# design.net
KiCad netlist of a schematic drawn in EasyEDA Pro
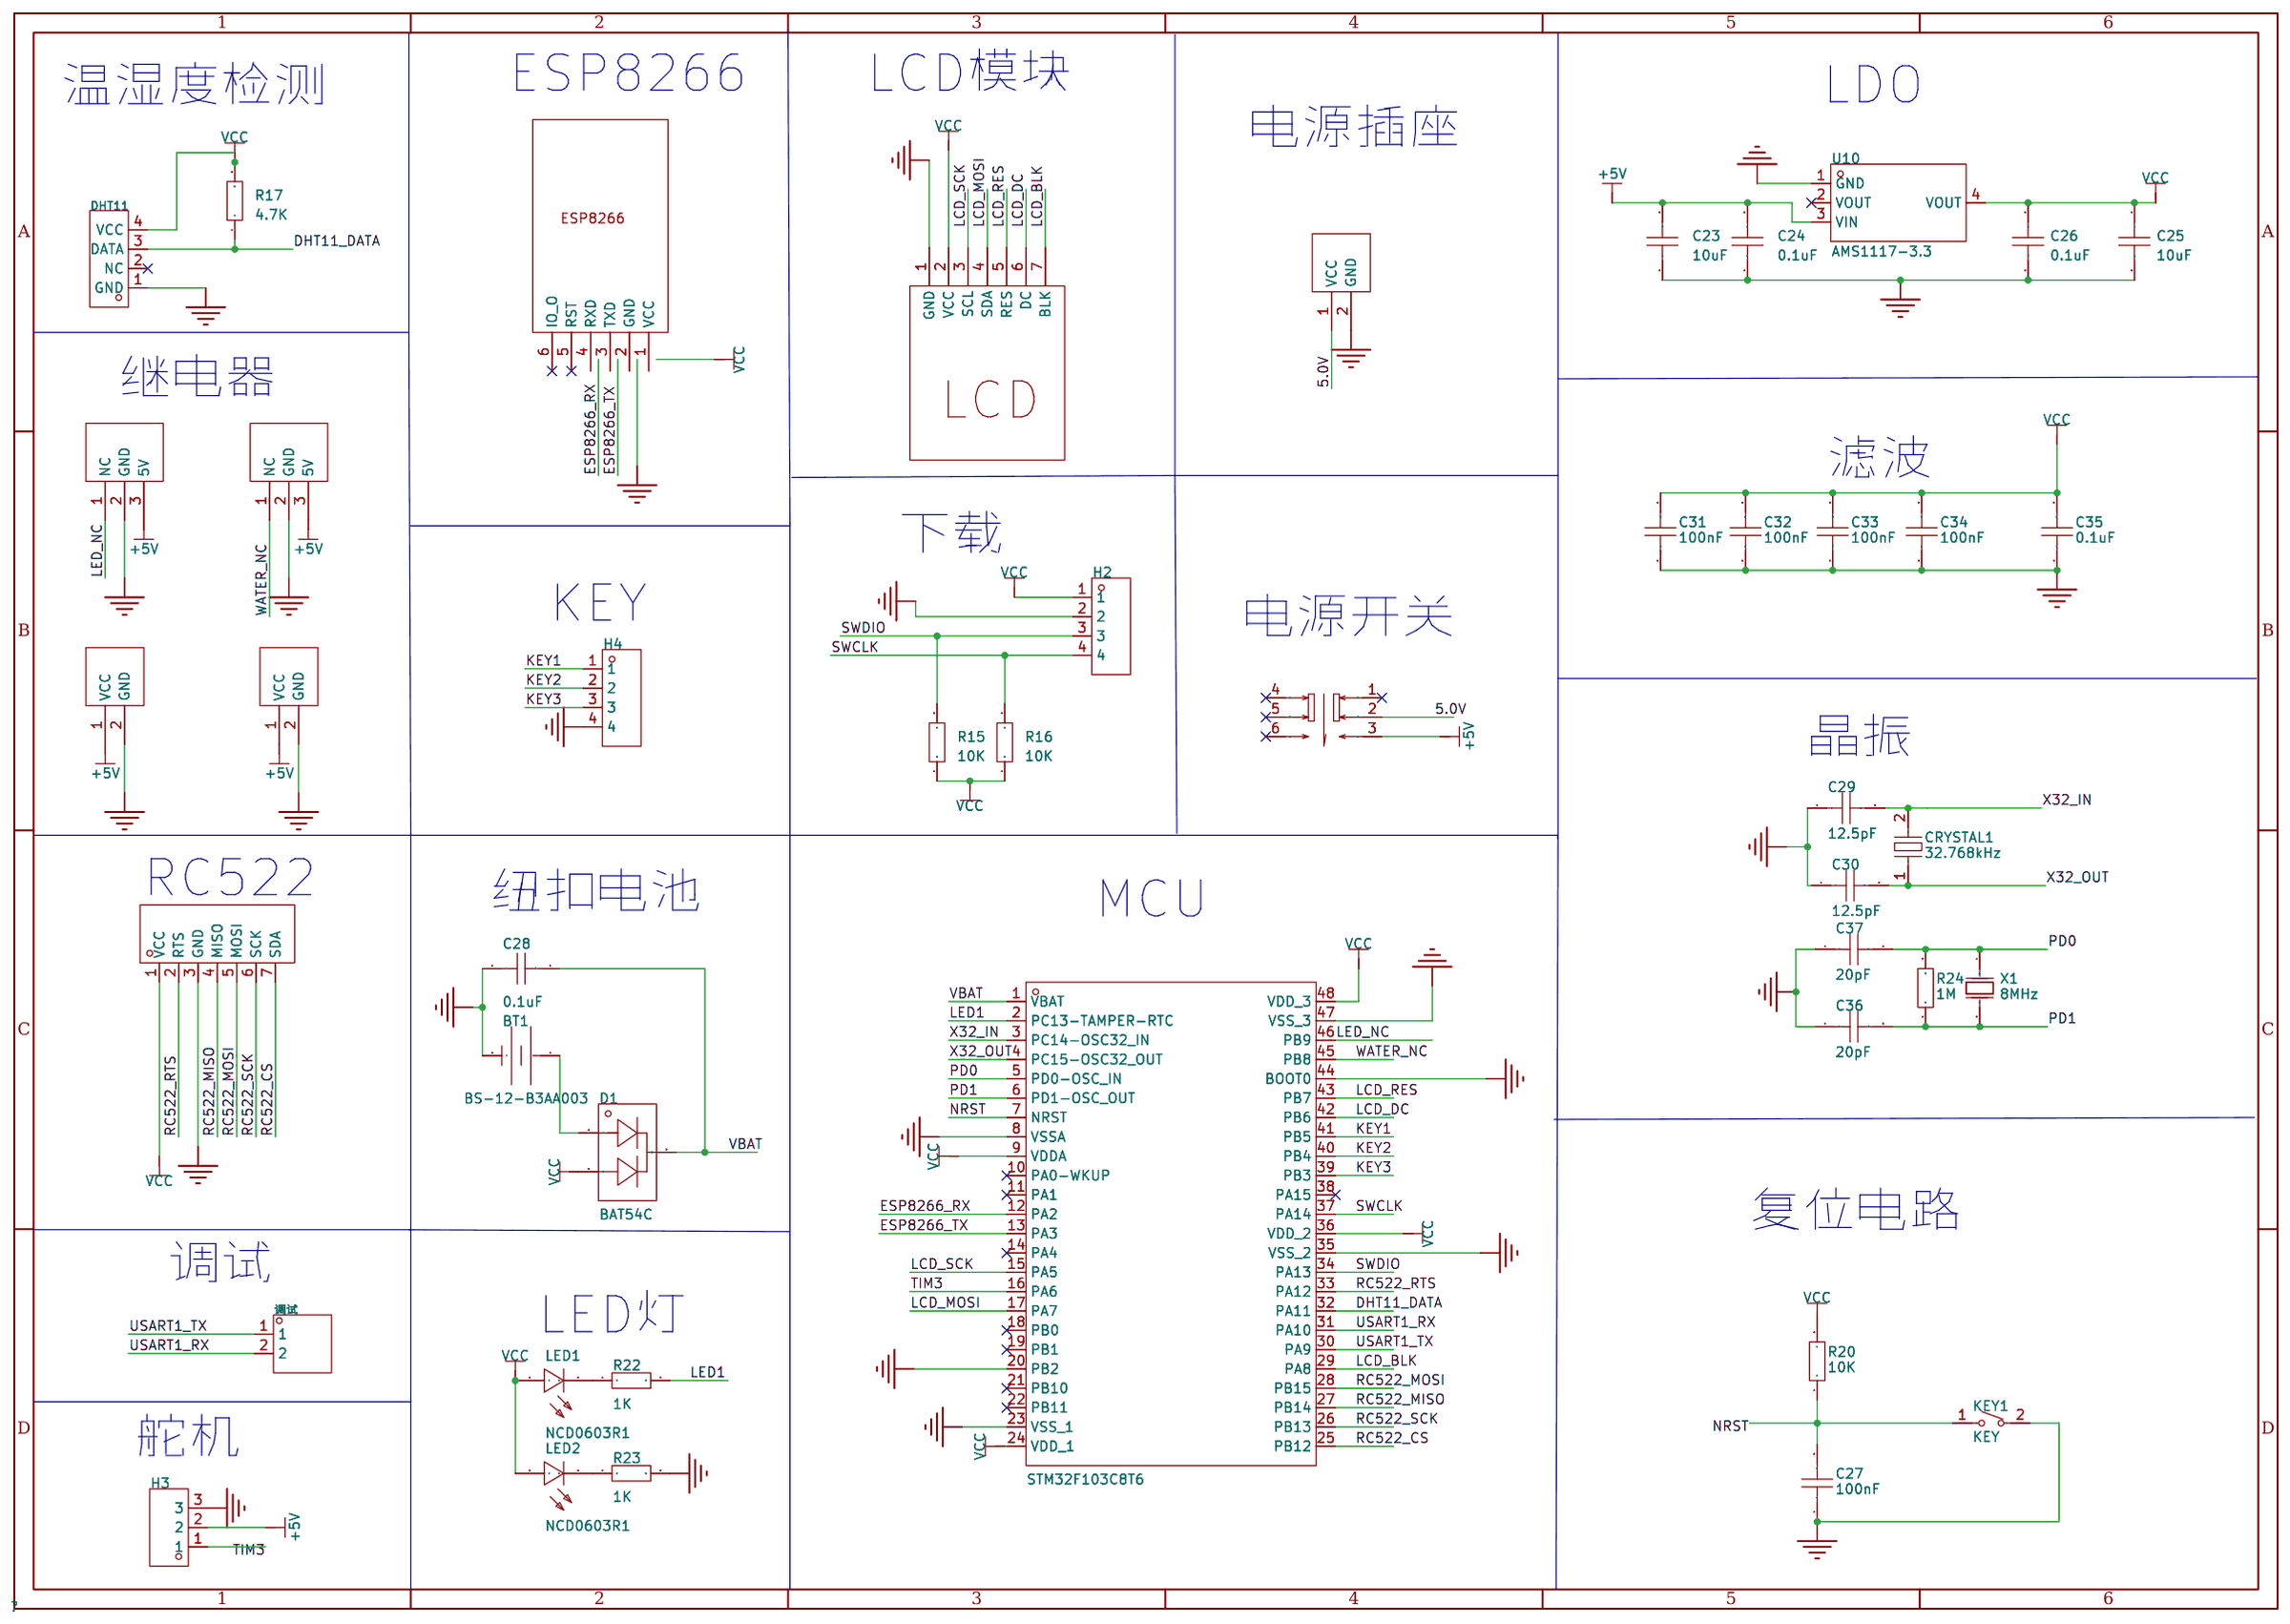
[diagram p0: schematic sheet]

(export (version "E")
  (design (tool "Eeschema 10.0.6"))
  (components
    (comp (ref "BT1")
      (value "BS-12-B3AA003")
      (footprint "easyedapro:BAT-SMD_BS-12-B3AA011")
      (description "连接器类型:电池底座;适用电池规格:CR1220;工作温度范围:-25°C~+85°C;")
      (fields (field (name "Manufacturer") "MYOUNG(美阳)"))
      (libsource (lib "easyedapro") (part "BS-12-B3AA003"))
    )
    (comp (ref "C23")
      (value "10uF")
      (footprint "easyedapro:C0402")
      (libsource (lib "easyedapro") (part "CapAcitance"))
    )
    (comp (ref "C24")
      (value "0.1uF")
      (footprint "easyedapro:C0402")
      (libsource (lib "easyedapro") (part "CapAcitance"))
    )
    (comp (ref "C25")
      (value "10uF")
      (footprint "easyedapro:C0402")
      (libsource (lib "easyedapro") (part "CapAcitance"))
    )
    (comp (ref "C26")
      (value "0.1uF")
      (footprint "easyedapro:C0402")
      (libsource (lib "easyedapro") (part "CapAcitance"))
    )
    (comp (ref "C27")
      (value "100nF")
      (footprint "easyedapro:C0402")
      (libsource (lib "easyedapro") (part "CapAcitance"))
    )
    (comp (ref "C28")
      (value "0.1uF")
      (footprint "easyedapro:C0402")
      (libsource (lib "easyedapro") (part "CapAcitance"))
    )
    (comp (ref "C29")
      (value "12.5pF")
      (footprint "easyedapro:C0402")
      (libsource (lib "easyedapro") (part "CapAcitance"))
    )
    (comp (ref "C30")
      (value "12.5pF")
      (footprint "easyedapro:C0402")
      (libsource (lib "easyedapro") (part "CapAcitance"))
    )
    (comp (ref "C31")
      (value "100nF")
      (footprint "easyedapro:C0402")
      (libsource (lib "easyedapro") (part "CapAcitance"))
    )
    (comp (ref "C32")
      (value "100nF")
      (footprint "easyedapro:C0402")
      (libsource (lib "easyedapro") (part "CapAcitance"))
    )
    (comp (ref "C33")
      (value "100nF")
      (footprint "easyedapro:C0402")
      (libsource (lib "easyedapro") (part "CapAcitance"))
    )
    (comp (ref "C34")
      (value "100nF")
      (footprint "easyedapro:C0402")
      (libsource (lib "easyedapro") (part "CapAcitance"))
    )
    (comp (ref "C35")
      (value "0.1uF")
      (footprint "easyedapro:C0402")
      (libsource (lib "easyedapro") (part "CapAcitance"))
    )
    (comp (ref "C36")
      (value "20pF")
      (footprint "easyedapro:C0402")
      (libsource (lib "easyedapro") (part "CapAcitance"))
    )
    (comp (ref "C37")
      (value "20pF")
      (footprint "easyedapro:C0402")
      (libsource (lib "easyedapro") (part "CapAcitance"))
    )
    (comp (ref "CRYSTAL1")
      (value "32.768kHz")
      (footprint "easyedapro:CRYSTAL-SMD_L3.2-W1.5-FC-135R32.7680KF-A3")
      (description "频率:32.768kHz;负载电容:12.5pF;频率公差:±20ppm;")
      (fields (field (name "Manufacturer Part") "DF2032K76812001") (field (name "Manufacturer") "HUAXIN(华昕)"))
      (libsource (lib "easyedapro") (part "DF2032K76812001"))
    )
    (comp (ref "D1")
      (value "BAT54C")
      (footprint "easyedapro:SOT-23-3_L2.9-W1.4-P1.91-LS2.6-BR")
      (description "二极管配置:1对共阴极;正向压降(Vf):1V@100mA;直流反向耐压(Vr):30V;平均整流电流(Io):200mA;")
      (fields (field (name "Manufacturer") "TWGMC(台湾迪嘉)"))
      (libsource (lib "easyedapro") (part "BAT54C_C727125"))
    )
    (comp (ref "DHT11")
      (value "~")
      (footprint "easyedapro:HDR-TH_4P-P2.54-V-F")
      (fields (field (name "Manufacturer Part") "2.54-1*4P母") (field (name "Manufacturer") "BOOMELE(博穆精密)"))
      (libsource (lib "easyedapro") (part "2.54-1*4P母"))
    )
    (comp (ref "H1")
      (value "~")
      (footprint "easyedapro:HDR-TH_7P-P2.54-V-M")
      (fields (field (name "Manufacturer Part") "PZ254V-11-07P") (field (name "Manufacturer") "XFCN(兴飞)"))
      (libsource (lib "easyedapro") (part "PZ254V-11-07P"))
    )
    (comp (ref "H2")
      (value "~")
      (footprint "easyedapro:HDR-TH_4P-P2.54-V-M")
      (libsource (lib "easyedapro") (part "PZ254V-11-04P"))
    )
    (comp (ref "H3")
      (value "~")
      (footprint "easyedapro:HDR-TH_3P-P2.54-V-M")
      (libsource (lib "easyedapro") (part "PZ254V-11-03P_C2937625"))
    )
    (comp (ref "H4")
      (value "~")
      (footprint "easyedapro:HDR-TH_4P-P2.54-V-M")
      (libsource (lib "easyedapro") (part "PZ254V-11-04P"))
    )
    (comp (ref "KEY1")
      (value "KEY")
      (footprint "easyedapro:SW-SMD_L6.0-W3.7-LS8.0")
      (libsource (lib "easyedapro") (part "KEY_C9900023212"))
    )
    (comp (ref "LED1")
      (value "NCD0603R1")
      (footprint "easyedapro:LED0603-RD_RED")
      (description "发光颜色:红色;功率:65mW;透镜颜色:无色透明;主波长:615nm~630nm;发光强度:80mcd~220mcd;发光角度:130°;工作温度:-30°C~+85°C;")
      (fields (field (name "Manufacturer") "国星光电"))
      (libsource (lib "easyedapro") (part "FC-DA1608HRK-620D"))
    )
    (comp (ref "LED2")
      (value "NCD0603R1")
      (footprint "easyedapro:LED0603-RD_RED")
      (description "发光颜色:红色;功率:65mW;透镜颜色:无色透明;主波长:615nm~630nm;发光强度:80mcd~220mcd;发光角度:130°;工作温度:-30°C~+85°C;")
      (fields (field (name "Manufacturer") "国星光电"))
      (libsource (lib "easyedapro") (part "FC-DA1608HRK-620D"))
    )
    (comp (ref "R15")
      (value "10K")
      (footprint "easyedapro:Res_1/8W")
      (libsource (lib "easyedapro") (part "电阻"))
    )
    (comp (ref "R16")
      (value "10K")
      (footprint "easyedapro:Res_1/8W")
      (libsource (lib "easyedapro") (part "电阻"))
    )
    (comp (ref "R17")
      (value "4.7K")
      (footprint "easyedapro:Res_1/8W")
      (libsource (lib "easyedapro") (part "电阻"))
    )
    (comp (ref "R20")
      (value "10K")
      (footprint "easyedapro:Res_1/8W")
      (libsource (lib "easyedapro") (part "电阻"))
    )
    (comp (ref "R22")
      (value "1K")
      (footprint "easyedapro:Res_1/8W")
      (libsource (lib "easyedapro") (part "电阻"))
    )
    (comp (ref "R23")
      (value "1K")
      (footprint "easyedapro:Res_1/8W")
      (libsource (lib "easyedapro") (part "电阻"))
    )
    (comp (ref "R24")
      (value "1M")
      (footprint "easyedapro:Res_1/8W")
      (libsource (lib "easyedapro") (part "电阻"))
    )
    (comp (ref "SW1")
      (value "TK-6700-1")
      (footprint "easyedapro:SW-TH_TK-6700-1")
      (fields (field (name "Manufacturer") "Yuandi(元迪)"))
      (libsource (lib "easyedapro") (part "TK-6700-1"))
    )
    (comp (ref "U1")
      (value "~")
      (footprint "easyedapro:正点原子ESP8266")
      (libsource (lib "easyedapro") (part "正点原子ESP8266"))
    )
    (comp (ref "U2")
      (value "~")
      (footprint "easyedapro:LCD-TFT")
      (libsource (lib "easyedapro") (part "LCD-TFT"))
    )
    (comp (ref "U3")
      (value "~")
      (footprint "easyedapro:电源2Pin")
      (libsource (lib "easyedapro") (part "电源2Pin"))
    )
    (comp (ref "U5")
      (value "~")
      (footprint "easyedapro:电源3Pin")
      (libsource (lib "easyedapro") (part "电源3Pin"))
    )
    (comp (ref "U6")
      (value "~")
      (footprint "easyedapro:电源3Pin")
      (libsource (lib "easyedapro") (part "电源3Pin"))
    )
    (comp (ref "U7")
      (value "~")
      (footprint "easyedapro:电源2Pin")
      (libsource (lib "easyedapro") (part "电源2Pin"))
    )
    (comp (ref "U8")
      (value "~")
      (footprint "easyedapro:电源2Pin")
      (libsource (lib "easyedapro") (part "电源2Pin"))
    )
    (comp (ref "U9")
      (value "STM32F103C8T6")
      (footprint "easyedapro:LQFP-48_L7.0-W7.0-P0.50-LS9.0-BL")
      (fields (field (name "Manufacturer") "ST(意法半导体)"))
      (libsource (lib "easyedapro") (part "STM32F103C8T6"))
    )
    (comp (ref "U10")
      (value "AMS1117-3.3")
      (footprint "easyedapro:SOT-223-3_L6.5-W3.4-P2.30-LS7.0-BR")
      (description "输出类型:固定;最大输入电压:-;输出电压:3.3V;输出电流:1A;电源纹波抑制比(PSRR):72dB@(120Hz);输出极性:正;")
      (fields (field (name "Manufacturer") "AMS"))
      (libsource (lib "easyedapro") (part "AMS1117-3.3"))
    )
    (comp (ref "X1")
      (value "8MHz")
      (footprint "easyedapro:CRYSTAL-SMD_L11.5-W4.8-LS12.7")
      (description "频率:8MHz;负载电容:20pF;频率公差:±20ppm;")
      (fields (field (name "Manufacturer Part") "X49SM8MSD2SC") (field (name "Manufacturer") "YXC(扬兴晶振)"))
      (libsource (lib "easyedapro") (part "X49SM8MSD2SC"))
    )
    (comp (ref "调试")
      (value "~")
      (footprint "easyedapro:HDR-TH_2P-P2.54-V-M-1")
      (libsource (lib "easyedapro") (part "210S-1*2P L=11.6MMGold-plated black"))
    )
  )
  (nets
    (net (code "1") (name "+5V") (class "Default")
      (node (ref "C23") (pin "2") (pinfunction "2_2") (pintype "input"))
      (node (ref "C24") (pin "2") (pinfunction "2_2") (pintype "input"))
      (node (ref "H3") (pin "2") (pinfunction "2_2") (pintype "input"))
      (node (ref "SW1") (pin "3") (pinfunction "3_3") (pintype "input"))
      (node (ref "U10") (pin "3") (pinfunction "VIN_3") (pintype "unspecified"))
      (node (ref "U5") (pin "3") (pinfunction "5V_3") (pintype "input"))
      (node (ref "U6") (pin "3") (pinfunction "5V_3") (pintype "input"))
      (node (ref "U7") (pin "1") (pinfunction "VCC_1") (pintype "input"))
      (node (ref "U8") (pin "1") (pinfunction "VCC_1") (pintype "input"))
    )
    (net (code "2") (name "/5.0V") (class "Default")
      (node (ref "SW1") (pin "2") (pinfunction "2_2") (pintype "input"))
      (node (ref "U3") (pin "1") (pinfunction "VCC_1") (pintype "input"))
    )
    (net (code "3") (name "/DHT11_DATA") (class "Default")
      (node (ref "DHT11") (pin "3") (pinfunction "DATA_3") (pintype "input"))
      (node (ref "R17") (pin "1") (pinfunction "1_1") (pintype "input"))
      (node (ref "U9") (pin "32") (pinfunction "PA11_32") (pintype "unspecified"))
    )
    (net (code "4") (name "/ESP8266_RX") (class "Default")
      (node (ref "U9") (pin "12") (pinfunction "PA2_12") (pintype "unspecified"))
    )
    (net (code "5") (name "/ESP8266_TX") (class "Default")
      (node (ref "U9") (pin "13") (pinfunction "PA3_13") (pintype "unspecified"))
    )
    (net (code "6") (name "/KEY1") (class "Default")
      (node (ref "H4") (pin "1") (pinfunction "1_1") (pintype "unspecified"))
      (node (ref "U9") (pin "41") (pinfunction "PB5_41") (pintype "unspecified"))
    )
    (net (code "7") (name "/KEY2") (class "Default")
      (node (ref "H4") (pin "2") (pinfunction "2_2") (pintype "unspecified"))
      (node (ref "U9") (pin "40") (pinfunction "PB4_40") (pintype "unspecified"))
    )
    (net (code "8") (name "/KEY3") (class "Default")
      (node (ref "H4") (pin "3") (pinfunction "3_3") (pintype "unspecified"))
      (node (ref "U9") (pin "39") (pinfunction "PB3_39") (pintype "unspecified"))
    )
    (net (code "9") (name "/LCD_BLK") (class "Default")
      (node (ref "U2") (pin "7") (pinfunction "BLK_7") (pintype "input"))
      (node (ref "U9") (pin "29") (pinfunction "PA8_29") (pintype "unspecified"))
    )
    (net (code "10") (name "/LCD_DC") (class "Default")
      (node (ref "U2") (pin "6") (pinfunction "DC_6") (pintype "input"))
      (node (ref "U9") (pin "42") (pinfunction "PB6_42") (pintype "unspecified"))
    )
    (net (code "11") (name "/LCD_MOSI") (class "Default")
      (node (ref "U2") (pin "4") (pinfunction "SDA_4") (pintype "input"))
      (node (ref "U9") (pin "17") (pinfunction "PA7_17") (pintype "unspecified"))
    )
    (net (code "12") (name "/LCD_RES") (class "Default")
      (node (ref "U2") (pin "5") (pinfunction "RES_5") (pintype "input"))
      (node (ref "U9") (pin "43") (pinfunction "PB7_43") (pintype "unspecified"))
    )
    (net (code "13") (name "/LCD_SCK") (class "Default")
      (node (ref "U2") (pin "3") (pinfunction "SCL_3") (pintype "input"))
      (node (ref "U9") (pin "15") (pinfunction "PA5_15") (pintype "unspecified"))
    )
    (net (code "14") (name "/LED1") (class "Default")
      (node (ref "R22") (pin "2") (pinfunction "2_2") (pintype "input"))
      (node (ref "U9") (pin "2") (pinfunction "PC13-TAMPER-RTC_2") (pintype "unspecified"))
    )
    (net (code "15") (name "/LED_NC") (class "Default")
      (node (ref "U5") (pin "1") (pinfunction "NC_1") (pintype "input"))
      (node (ref "U9") (pin "46") (pinfunction "PB9_46") (pintype "unspecified"))
    )
    (net (code "16") (name "/NRST") (class "Default")
      (node (ref "C27") (pin "2") (pinfunction "2_2") (pintype "input"))
      (node (ref "KEY1") (pin "1") (pinfunction "1_1") (pintype "input"))
      (node (ref "R20") (pin "1") (pinfunction "1_1") (pintype "input"))
      (node (ref "U9") (pin "7") (pinfunction "NRST_7") (pintype "unspecified"))
    )
    (net (code "17") (name "/PD0") (class "Default")
      (node (ref "C37") (pin "2") (pinfunction "2_2") (pintype "input"))
      (node (ref "R24") (pin "2") (pinfunction "2_2") (pintype "input"))
      (node (ref "U9") (pin "5") (pinfunction "PD0-OSC_IN_5") (pintype "unspecified"))
      (node (ref "X1") (pin "1") (pinfunction "OSC1_1") (pintype "input"))
    )
    (net (code "18") (name "/PD1") (class "Default")
      (node (ref "C36") (pin "2") (pinfunction "2_2") (pintype "input"))
      (node (ref "R24") (pin "1") (pinfunction "1_1") (pintype "input"))
      (node (ref "U9") (pin "6") (pinfunction "PD1-OSC_OUT_6") (pintype "unspecified"))
      (node (ref "X1") (pin "2") (pinfunction "OSC2_2") (pintype "input"))
    )
    (net (code "19") (name "/RC522_CS") (class "Default")
      (node (ref "H1") (pin "7") (pinfunction "SDA_7") (pintype "input"))
      (node (ref "U9") (pin "25") (pinfunction "PB12_25") (pintype "unspecified"))
    )
    (net (code "20") (name "/RC522_MISO") (class "Default")
      (node (ref "H1") (pin "4") (pinfunction "MISO_4") (pintype "input"))
      (node (ref "U9") (pin "27") (pinfunction "PB14_27") (pintype "unspecified"))
    )
    (net (code "21") (name "/RC522_MOSI") (class "Default")
      (node (ref "H1") (pin "5") (pinfunction "MOSI_5") (pintype "input"))
      (node (ref "U9") (pin "28") (pinfunction "PB15_28") (pintype "unspecified"))
    )
    (net (code "22") (name "/RC522_RTS") (class "Default")
      (node (ref "H1") (pin "2") (pinfunction "RTS_2") (pintype "input"))
      (node (ref "U9") (pin "33") (pinfunction "PA12_33") (pintype "unspecified"))
    )
    (net (code "23") (name "/RC522_SCK") (class "Default")
      (node (ref "H1") (pin "6") (pinfunction "SCK_6") (pintype "input"))
      (node (ref "U9") (pin "26") (pinfunction "PB13_26") (pintype "unspecified"))
    )
    (net (code "24") (name "/SWCLK") (class "Default")
      (node (ref "H2") (pin "4") (pinfunction "4_4") (pintype "unspecified"))
      (node (ref "R16") (pin "2") (pinfunction "2_2") (pintype "input"))
      (node (ref "U9") (pin "37") (pinfunction "PA14_37") (pintype "unspecified"))
    )
    (net (code "25") (name "/SWDIO") (class "Default")
      (node (ref "H2") (pin "3") (pinfunction "3_3") (pintype "unspecified"))
      (node (ref "R15") (pin "2") (pinfunction "2_2") (pintype "input"))
      (node (ref "U9") (pin "34") (pinfunction "PA13_34") (pintype "unspecified"))
    )
    (net (code "26") (name "/TIM3") (class "Default")
      (node (ref "H3") (pin "1") (pinfunction "1_1") (pintype "input"))
      (node (ref "U9") (pin "16") (pinfunction "PA6_16") (pintype "unspecified"))
    )
    (net (code "27") (name "/USART1_RX") (class "Default")
      (node (ref "U9") (pin "31") (pinfunction "PA10_31") (pintype "unspecified"))
      (node (ref "调试") (pin "2") (pinfunction "2_2") (pintype "input"))
    )
    (net (code "28") (name "/USART1_TX") (class "Default")
      (node (ref "U9") (pin "30") (pinfunction "PA9_30") (pintype "unspecified"))
      (node (ref "调试") (pin "1") (pinfunction "1_1") (pintype "input"))
    )
    (net (code "29") (name "/VBAT") (class "Default")
      (node (ref "C28") (pin "2") (pinfunction "2_2") (pintype "input"))
      (node (ref "D1") (pin "3") (pinfunction "3_3") (pintype "unspecified"))
      (node (ref "U9") (pin "1") (pinfunction "VBAT_1") (pintype "unspecified"))
    )
    (net (code "30") (name "/WATER_NC") (class "Default")
      (node (ref "U6") (pin "1") (pinfunction "NC_1") (pintype "input"))
      (node (ref "U9") (pin "45") (pinfunction "PB8_45") (pintype "unspecified"))
    )
    (net (code "31") (name "/X32_IN") (class "Default")
      (node (ref "C29") (pin "2") (pinfunction "2_2") (pintype "input"))
      (node (ref "CRYSTAL1") (pin "2") (pinfunction "2_2") (pintype "unspecified"))
      (node (ref "U9") (pin "3") (pinfunction "PC14-OSC32_IN_3") (pintype "unspecified"))
    )
    (net (code "32") (name "/X32_OUT") (class "Default")
      (node (ref "C30") (pin "2") (pinfunction "2_2") (pintype "input"))
      (node (ref "CRYSTAL1") (pin "1") (pinfunction "1_1") (pintype "unspecified"))
      (node (ref "U9") (pin "4") (pinfunction "PC15-OSC32_OUT_4") (pintype "unspecified"))
    )
    (net (code "33") (name "GND") (class "Default")
      (node (ref "BT1") (pin "2") (pinfunction "-_2") (pintype "unspecified"))
      (node (ref "C23") (pin "1") (pinfunction "1_1") (pintype "input"))
      (node (ref "C24") (pin "1") (pinfunction "1_1") (pintype "input"))
      (node (ref "C25") (pin "2") (pinfunction "2_2") (pintype "input"))
      (node (ref "C26") (pin "2") (pinfunction "2_2") (pintype "input"))
      (node (ref "C27") (pin "1") (pinfunction "1_1") (pintype "input"))
      (node (ref "C28") (pin "1") (pinfunction "1_1") (pintype "input"))
      (node (ref "C29") (pin "1") (pinfunction "1_1") (pintype "input"))
      (node (ref "C30") (pin "1") (pinfunction "1_1") (pintype "input"))
      (node (ref "C31") (pin "1") (pinfunction "1_1") (pintype "input"))
      (node (ref "C32") (pin "1") (pinfunction "1_1") (pintype "input"))
      (node (ref "C33") (pin "1") (pinfunction "1_1") (pintype "input"))
      (node (ref "C34") (pin "1") (pinfunction "1_1") (pintype "input"))
      (node (ref "C35") (pin "1") (pinfunction "1_1") (pintype "input"))
      (node (ref "C36") (pin "1") (pinfunction "1_1") (pintype "input"))
      (node (ref "C37") (pin "1") (pinfunction "1_1") (pintype "input"))
      (node (ref "DHT11") (pin "1") (pinfunction "GND_1") (pintype "input"))
      (node (ref "H1") (pin "3") (pinfunction "GND_3") (pintype "input"))
      (node (ref "H2") (pin "2") (pinfunction "2_2") (pintype "unspecified"))
      (node (ref "H3") (pin "3") (pinfunction "3_3") (pintype "input"))
      (node (ref "H4") (pin "4") (pinfunction "4_4") (pintype "unspecified"))
      (node (ref "KEY1") (pin "2") (pinfunction "2_2") (pintype "input"))
      (node (ref "R23") (pin "2") (pinfunction "2_2") (pintype "input"))
      (node (ref "U10") (pin "1") (pinfunction "GND_1") (pintype "unspecified"))
      (node (ref "U2") (pin "1") (pinfunction "GND_1") (pintype "input"))
      (node (ref "U3") (pin "2") (pinfunction "GND_2") (pintype "input"))
      (node (ref "U5") (pin "2") (pinfunction "GND_2") (pintype "input"))
      (node (ref "U6") (pin "2") (pinfunction "GND_2") (pintype "input"))
      (node (ref "U7") (pin "2") (pinfunction "GND_2") (pintype "input"))
      (node (ref "U8") (pin "2") (pinfunction "GND_2") (pintype "input"))
      (node (ref "U9") (pin "20") (pinfunction "PB2_20") (pintype "unspecified"))
      (node (ref "U9") (pin "23") (pinfunction "VSS_1_23") (pintype "unspecified"))
      (node (ref "U9") (pin "35") (pinfunction "VSS_2_35") (pintype "unspecified"))
      (node (ref "U9") (pin "44") (pinfunction "BOOT0_44") (pintype "unspecified"))
      (node (ref "U9") (pin "47") (pinfunction "VSS_3_47") (pintype "unspecified"))
      (node (ref "U9") (pin "8") (pinfunction "VSSA_8") (pintype "unspecified"))
    )
    (net (code "34") (name "Net-(BT1-+)") (class "Default")
      (node (ref "BT1") (pin "1") (pinfunction "+_1") (pintype "unspecified"))
      (node (ref "D1") (pin "1") (pinfunction "1_1") (pintype "unspecified"))
    )
    (net (code "35") (name "Net-(LED1-K)") (class "Default")
      (node (ref "LED1") (pin "1") (pinfunction "K_1") (pintype "input"))
      (node (ref "R22") (pin "1") (pinfunction "1_1") (pintype "input"))
    )
    (net (code "36") (name "Net-(LED2-K)") (class "Default")
      (node (ref "LED2") (pin "1") (pinfunction "K_1") (pintype "input"))
      (node (ref "R23") (pin "1") (pinfunction "1_1") (pintype "input"))
    )
    (net (code "37") (name "VCC") (class "Default")
      (node (ref "C25") (pin "1") (pinfunction "1_1") (pintype "input"))
      (node (ref "C26") (pin "1") (pinfunction "1_1") (pintype "input"))
      (node (ref "C31") (pin "2") (pinfunction "2_2") (pintype "input"))
      (node (ref "C32") (pin "2") (pinfunction "2_2") (pintype "input"))
      (node (ref "C33") (pin "2") (pinfunction "2_2") (pintype "input"))
      (node (ref "C34") (pin "2") (pinfunction "2_2") (pintype "input"))
      (node (ref "C35") (pin "2") (pinfunction "2_2") (pintype "input"))
      (node (ref "D1") (pin "2") (pinfunction "2_2") (pintype "unspecified"))
      (node (ref "DHT11") (pin "4") (pinfunction "VCC_4") (pintype "input"))
      (node (ref "H1") (pin "1") (pinfunction "VCC_1") (pintype "input"))
      (node (ref "H2") (pin "1") (pinfunction "1_1") (pintype "unspecified"))
      (node (ref "LED1") (pin "2") (pinfunction "A_2") (pintype "input"))
      (node (ref "LED2") (pin "2") (pinfunction "A_2") (pintype "input"))
      (node (ref "R15") (pin "1") (pinfunction "1_1") (pintype "input"))
      (node (ref "R16") (pin "1") (pinfunction "1_1") (pintype "input"))
      (node (ref "R17") (pin "2") (pinfunction "2_2") (pintype "input"))
      (node (ref "R20") (pin "2") (pinfunction "2_2") (pintype "input"))
      (node (ref "U10") (pin "4") (pinfunction "VOUT_4") (pintype "unspecified"))
      (node (ref "U2") (pin "2") (pinfunction "VCC_2") (pintype "input"))
      (node (ref "U9") (pin "24") (pinfunction "VDD_1_24") (pintype "unspecified"))
      (node (ref "U9") (pin "36") (pinfunction "VDD_2_36") (pintype "unspecified"))
      (node (ref "U9") (pin "48") (pinfunction "VDD_3_48") (pintype "unspecified"))
      (node (ref "U9") (pin "9") (pinfunction "VDDA_9") (pintype "unspecified"))
    )
    (net (code "38") (name "unconnected-(DHT11-NC-Pad2)") (class "Default")
      (node (ref "DHT11") (pin "2") (pinfunction "NC_2") (pintype "input+no_connect"))
    )
    (net (code "39") (name "unconnected-(SW1-Pad1)") (class "Default")
      (node (ref "SW1") (pin "1") (pinfunction "1_1") (pintype "input+no_connect"))
    )
    (net (code "40") (name "unconnected-(SW1-Pad4)") (class "Default")
      (node (ref "SW1") (pin "4") (pinfunction "4_4") (pintype "input+no_connect"))
    )
    (net (code "41") (name "unconnected-(SW1-Pad5)") (class "Default")
      (node (ref "SW1") (pin "5") (pinfunction "5_5") (pintype "input+no_connect"))
    )
    (net (code "42") (name "unconnected-(SW1-Pad6)") (class "Default")
      (node (ref "SW1") (pin "6") (pinfunction "6_6") (pintype "input+no_connect"))
    )
    (net (code "43") (name "unconnected-(U1-GND-Pad2)") (class "Default")
      (node (ref "U1") (pin "2") (pinfunction "GND_2") (pintype "input"))
    )
    (net (code "44") (name "unconnected-(U1-IO_O-Pad6)") (class "Default")
      (node (ref "U1") (pin "6") (pinfunction "IO_O_6") (pintype "input+no_connect"))
    )
    (net (code "45") (name "unconnected-(U1-RST-Pad5)") (class "Default")
      (node (ref "U1") (pin "5") (pinfunction "RST_5") (pintype "input+no_connect"))
    )
    (net (code "46") (name "unconnected-(U1-RXD-Pad4)") (class "Default")
      (node (ref "U1") (pin "4") (pinfunction "RXD_4") (pintype "input"))
    )
    (net (code "47") (name "unconnected-(U1-TXD-Pad3)") (class "Default")
      (node (ref "U1") (pin "3") (pinfunction "TXD_3") (pintype "input"))
    )
    (net (code "48") (name "unconnected-(U1-VCC-Pad1)") (class "Default")
      (node (ref "U1") (pin "1") (pinfunction "VCC_1") (pintype "input"))
    )
    (net (code "49") (name "unconnected-(U9-PA0-WKUP-Pad10)") (class "Default")
      (node (ref "U9") (pin "10") (pinfunction "PA0-WKUP_10") (pintype "unspecified+no_connect"))
    )
    (net (code "50") (name "unconnected-(U9-PA1-Pad11)") (class "Default")
      (node (ref "U9") (pin "11") (pinfunction "PA1_11") (pintype "unspecified+no_connect"))
    )
    (net (code "51") (name "unconnected-(U9-PA4-Pad14)") (class "Default")
      (node (ref "U9") (pin "14") (pinfunction "PA4_14") (pintype "unspecified+no_connect"))
    )
    (net (code "52") (name "unconnected-(U9-PA15-Pad38)") (class "Default")
      (node (ref "U9") (pin "38") (pinfunction "PA15_38") (pintype "unspecified+no_connect"))
    )
    (net (code "53") (name "unconnected-(U9-PB0-Pad18)") (class "Default")
      (node (ref "U9") (pin "18") (pinfunction "PB0_18") (pintype "unspecified+no_connect"))
    )
    (net (code "54") (name "unconnected-(U9-PB1-Pad19)") (class "Default")
      (node (ref "U9") (pin "19") (pinfunction "PB1_19") (pintype "unspecified+no_connect"))
    )
    (net (code "55") (name "unconnected-(U9-PB10-Pad21)") (class "Default")
      (node (ref "U9") (pin "21") (pinfunction "PB10_21") (pintype "unspecified+no_connect"))
    )
    (net (code "56") (name "unconnected-(U9-PB11-Pad22)") (class "Default")
      (node (ref "U9") (pin "22") (pinfunction "PB11_22") (pintype "unspecified+no_connect"))
    )
    (net (code "57") (name "unconnected-(U10-VOUT-Pad2)") (class "Default")
      (node (ref "U10") (pin "2") (pinfunction "VOUT_2") (pintype "unspecified+no_connect"))
    )
  )
)
